# RobotComputerVision_1_1.net
KiCad netlist of a schematic drawn in Altium Designer
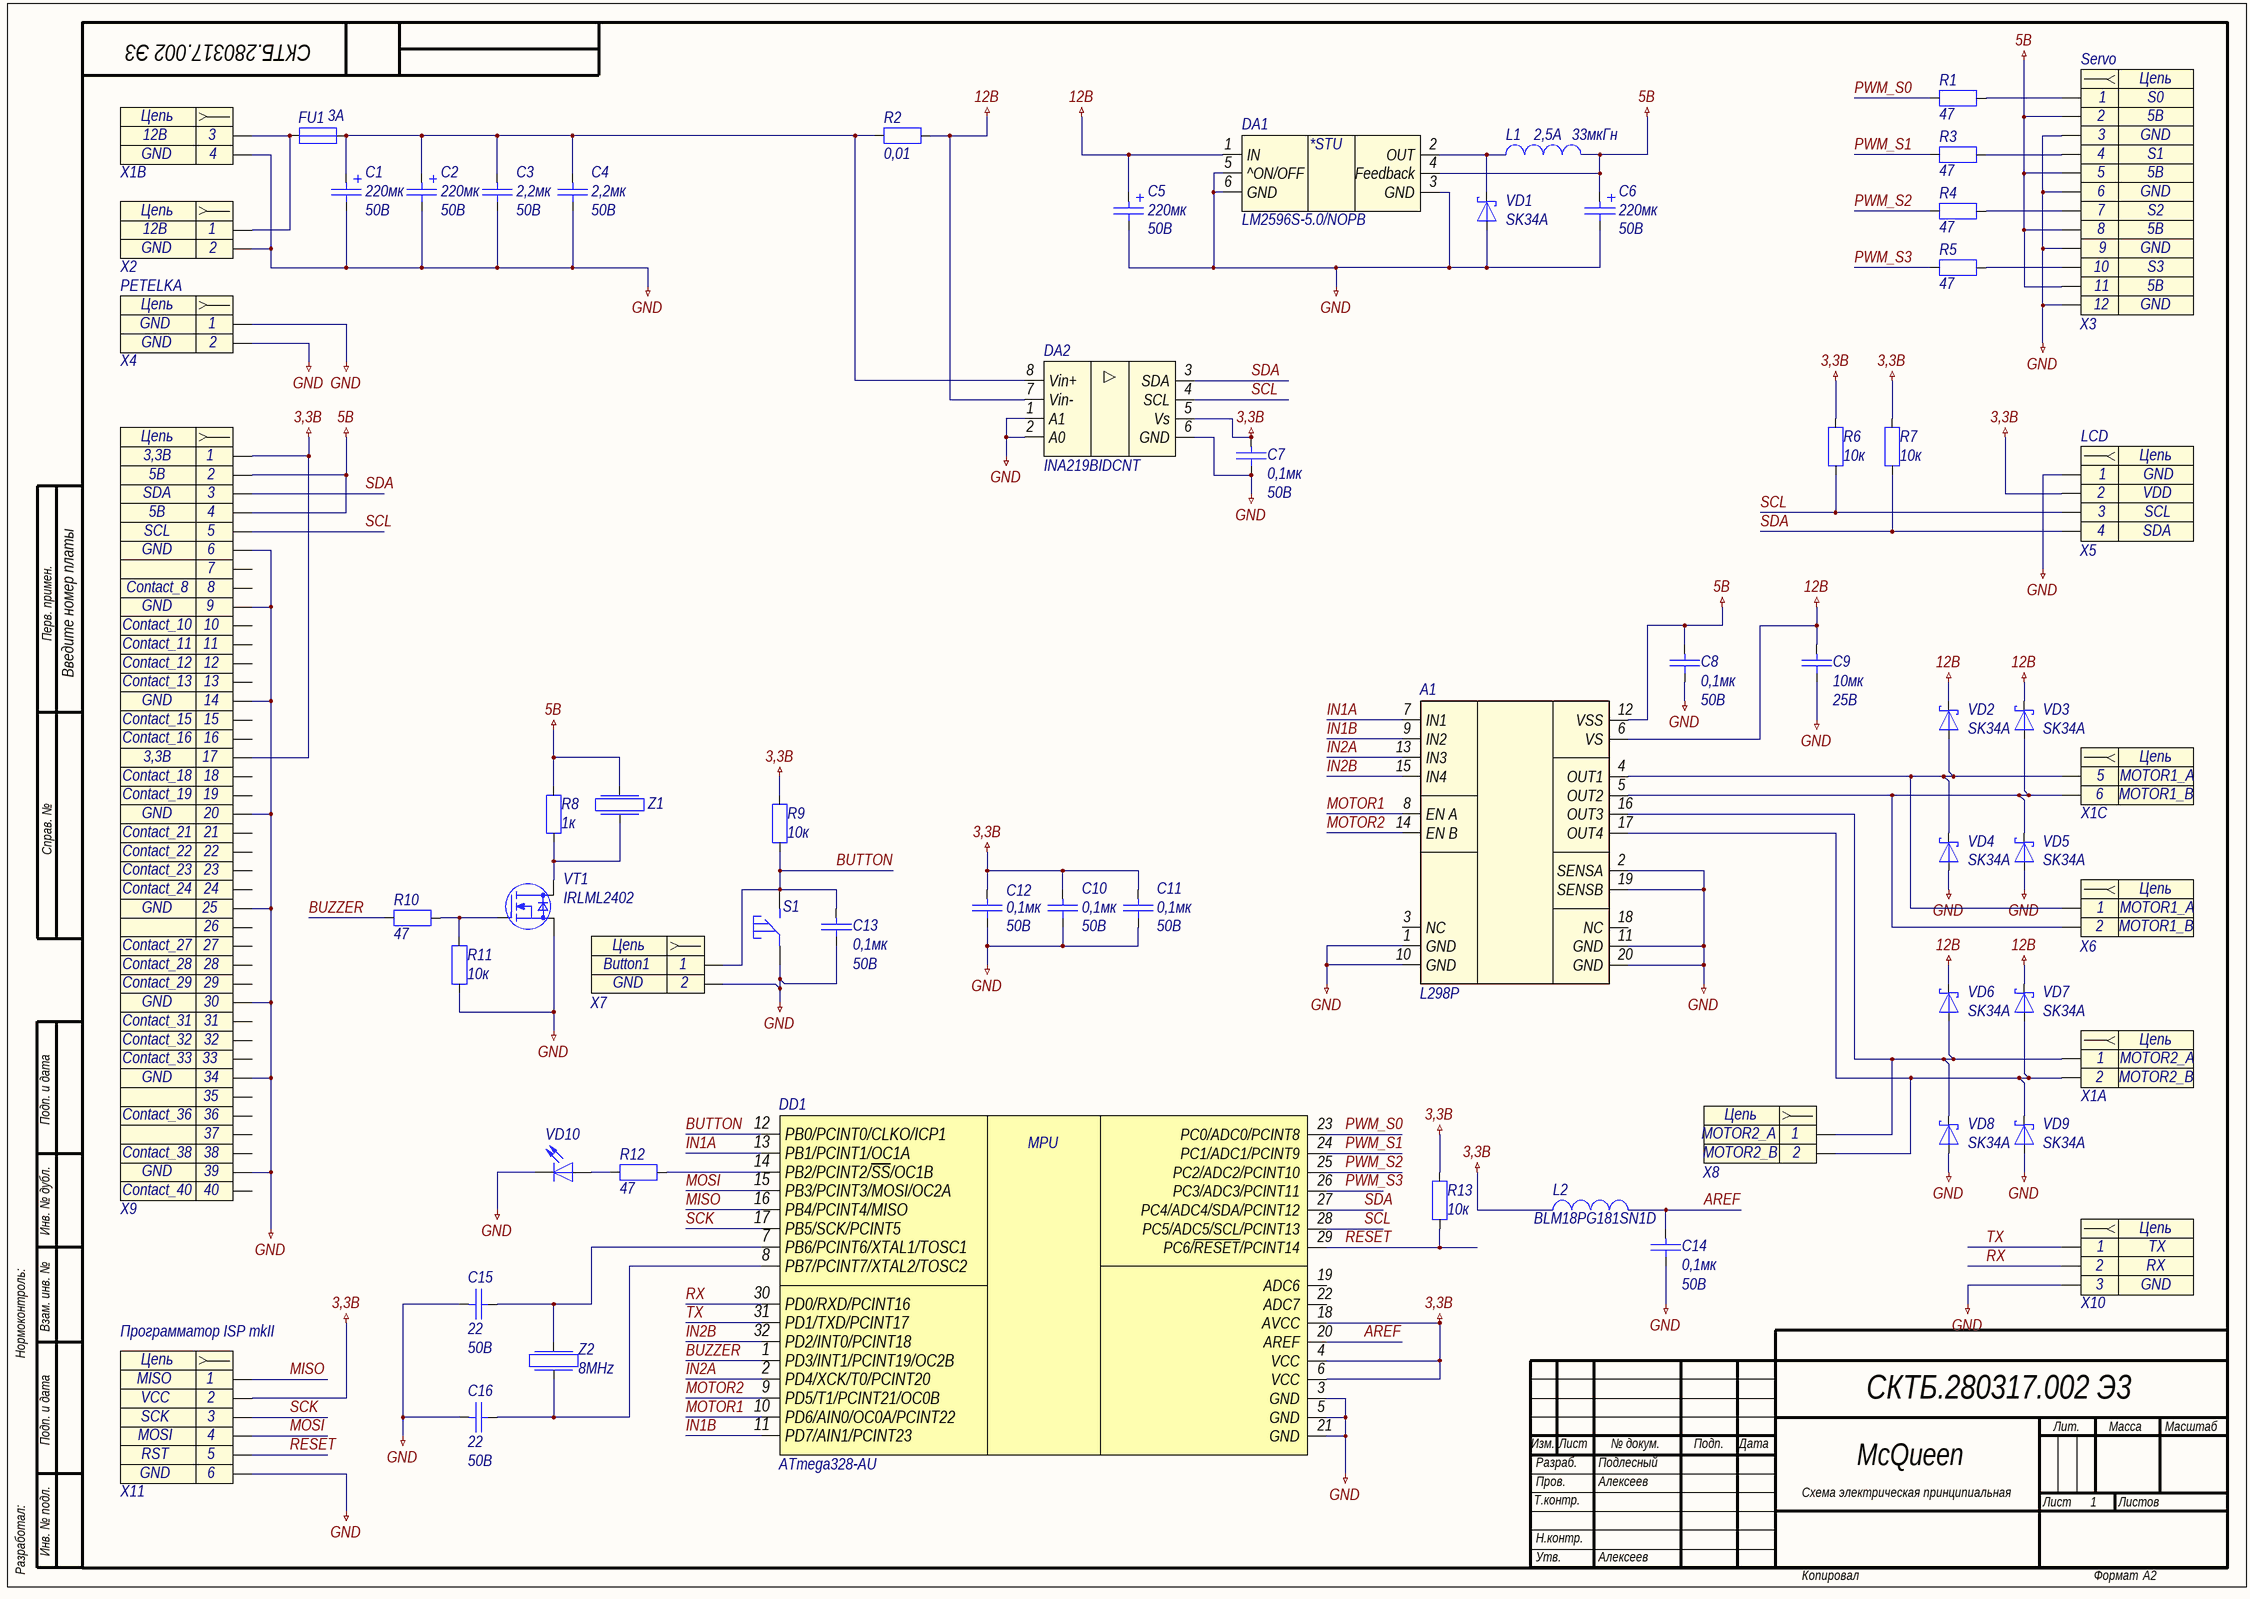
[diagram p0: RobotComputerVision_1.1.SchDoc]

(export (version "E")
  (design (tool "Eeschema 10.0.6"))
  (components
    (comp (ref "A1")
      (value "L298P")
      (footprint "ZabugorLib:POWERSO20_N")
      (description "FULL BRIDGE DC MOTOR DRIVER")
      (libsource (lib "ZabugorLib") (part "L298"))
    )
    (comp (ref "C1")
      (value "220мк")
      (footprint "ZabugorLib:Cap_SMD_radial_polar(10x10.5)")
      (description "Конденсатор полярный")
      (fields (field (name "VOLTAGE") "50В"))
      (libsource (lib "ZabugorLib") (part "Capacitor_pol"))
    )
    (comp (ref "C2")
      (value "220мк")
      (footprint "ZabugorLib:Cap_SMD_radial_polar(10x10.5)")
      (description "Конденсатор полярный")
      (fields (field (name "VOLTAGE") "50В"))
      (libsource (lib "ZabugorLib") (part "Capacitor_pol"))
    )
    (comp (ref "C3")
      (value "2,2мк")
      (footprint "ZabugorLib:C0805")
      (description "Конденсатор")
      (fields (field (name "VOLTAGE") "50В"))
      (libsource (lib "ZabugorLib") (part "Capacitor"))
    )
    (comp (ref "C4")
      (value "2,2мк")
      (footprint "ZabugorLib:C0805")
      (description "Конденсатор")
      (fields (field (name "VOLTAGE") "50В"))
      (libsource (lib "ZabugorLib") (part "Capacitor"))
    )
    (comp (ref "C5")
      (value "220мк")
      (footprint "ZabugorLib:Cap_SMD_radial_polar(10x10.5)")
      (description "Конденсатор полярный")
      (fields (field (name "VOLTAGE") "50В"))
      (libsource (lib "ZabugorLib") (part "Capacitor_pol"))
    )
    (comp (ref "C6")
      (value "220мк")
      (footprint "ZabugorLib:Cap_SMD_radial_polar(10x10.5)")
      (description "Конденсатор полярный")
      (fields (field (name "VOLTAGE") "50В"))
      (libsource (lib "ZabugorLib") (part "Capacitor_pol"))
    )
    (comp (ref "C7")
      (value "0,1мк")
      (footprint "ZabugorLib:C0805")
      (description "Конденсатор")
      (fields (field (name "VOLTAGE") "50В"))
      (libsource (lib "ZabugorLib") (part "Capacitor"))
    )
    (comp (ref "C8")
      (value "0,1мк")
      (footprint "ZabugorLib:C0805")
      (description "Конденсатор")
      (fields (field (name "VOLTAGE") "50В"))
      (libsource (lib "ZabugorLib") (part "Capacitor"))
    )
    (comp (ref "C9")
      (value "10мк")
      (footprint "ZabugorLib:C1210")
      (description "Конденсатор")
      (fields (field (name "VOLTAGE") "25В"))
      (libsource (lib "ZabugorLib") (part "Capacitor"))
    )
    (comp (ref "C10")
      (value "0,1мк")
      (footprint "ZabugorLib:C0805")
      (description "Конденсатор")
      (fields (field (name "VOLTAGE") "50В"))
      (libsource (lib "ZabugorLib") (part "Capacitor"))
    )
    (comp (ref "C11")
      (value "0,1мк")
      (footprint "ZabugorLib:C0805")
      (description "Конденсатор")
      (fields (field (name "VOLTAGE") "50В"))
      (libsource (lib "ZabugorLib") (part "Capacitor"))
    )
    (comp (ref "C12")
      (value "0,1мк")
      (footprint "ZabugorLib:C0805")
      (description "Конденсатор")
      (fields (field (name "VOLTAGE") "50В"))
      (libsource (lib "ZabugorLib") (part "Capacitor"))
    )
    (comp (ref "C13")
      (value "0,1мк")
      (footprint "ZabugorLib:C0805")
      (description "Конденсатор")
      (fields (field (name "VOLTAGE") "50В"))
      (libsource (lib "ZabugorLib") (part "Capacitor"))
    )
    (comp (ref "C14")
      (value "0,1мк")
      (footprint "ZabugorLib:C0805")
      (description "Конденсатор")
      (fields (field (name "VOLTAGE") "50В"))
      (libsource (lib "ZabugorLib") (part "Capacitor"))
    )
    (comp (ref "C15")
      (value "22")
      (footprint "ZabugorLib:C0805")
      (description "Конденсатор")
      (fields (field (name "VOLTAGE") "50В"))
      (libsource (lib "ZabugorLib") (part "Capacitor"))
    )
    (comp (ref "C16")
      (value "22")
      (footprint "ZabugorLib:C0805")
      (description "Конденсатор")
      (fields (field (name "VOLTAGE") "50В"))
      (libsource (lib "ZabugorLib") (part "Capacitor"))
    )
    (comp (ref "DA1")
      (value "LM2596S-5.0/NOPB")
      (footprint "ZabugorLib:TO-263")
      (description "3-A Step-Down Voltage Regulator")
      (libsource (lib "ZabugorLib") (part "LM2596"))
    )
    (comp (ref "DA2")
      (value "INA219BIDCNT")
      (footprint "ZabugorLib:SO8")
      (description "Токочувствительный усилитель")
      (libsource (lib "ZabugorLib") (part "INA219"))
    )
    (comp (ref "DD1")
      (value "ATmega328-AU")
      (footprint "ZabugorLib:TQFP-32")
      (description "Микроконтроллер 8-Бит, AVR, 16МГц, 8КБ Flash")
      (fields (field (name "NAME") "ATmega328-AU"))
      (libsource (lib "ZabugorLib") (part "ATmega328-AU"))
    )
    (comp (ref "FU1")
      (value "3А")
      (footprint "ZabugorLib:MF-R300")
      (description "Предохранитель")
      (fields (field (name "Comment") "MF-R300"))
      (libsource (lib "ZabugorLib") (part "Fuse"))
    )
    (comp (ref "L1")
      (value "33мкГн")
      (footprint "ZabugorLib:SRR1208")
      (description "Катушка индуктивности")
      (fields (field (name "IMAX") "2,5А"))
      (libsource (lib "ZabugorLib") (part "Inductor"))
    )
    (comp (ref "L2")
      (value "~")
      (footprint "ZabugorLib:L0603")
      (description "Катушка индуктивности")
      (fields (field (name "NAME") "BLM18PG181SN1D"))
      (libsource (lib "ZabugorLib") (part "Inductor"))
    )
    (comp (ref "R1")
      (value "47")
      (footprint "ZabugorLib:R0805")
      (description "Резистор")
      (libsource (lib "ZabugorLib") (part "Resistor"))
    )
    (comp (ref "R2")
      (value "0,01")
      (footprint "ZabugorLib:R2512")
      (description "Резистор")
      (libsource (lib "") (part "Resistor_2"))
    )
    (comp (ref "R3")
      (value "47")
      (footprint "ZabugorLib:R0805")
      (description "Резистор")
      (libsource (lib "ZabugorLib") (part "Resistor"))
    )
    (comp (ref "R4")
      (value "47")
      (footprint "ZabugorLib:R0805")
      (description "Резистор")
      (libsource (lib "ZabugorLib") (part "Resistor"))
    )
    (comp (ref "R5")
      (value "47")
      (footprint "ZabugorLib:R0805")
      (description "Резистор")
      (libsource (lib "ZabugorLib") (part "Resistor"))
    )
    (comp (ref "R6")
      (value "10к")
      (footprint "ZabugorLib:R0805")
      (description "Резистор")
      (libsource (lib "") (part "Resistor_2"))
    )
    (comp (ref "R7")
      (value "10к")
      (footprint "ZabugorLib:R0805")
      (description "Резистор")
      (libsource (lib "") (part "Resistor_2"))
    )
    (comp (ref "R8")
      (value "1к")
      (footprint "ZabugorLib:R0805")
      (description "Резистор")
      (libsource (lib "ZabugorLib") (part "Resistor"))
    )
    (comp (ref "R9")
      (value "10к")
      (footprint "ZabugorLib:R0805")
      (description "Резистор")
      (libsource (lib "ZabugorLib") (part "Resistor"))
    )
    (comp (ref "R10")
      (value "47")
      (footprint "ZabugorLib:R0805")
      (description "Резистор")
      (libsource (lib "") (part "Resistor_1"))
    )
    (comp (ref "R11")
      (value "10к")
      (footprint "ZabugorLib:R0805")
      (description "Резистор")
      (libsource (lib "ZabugorLib") (part "Resistor"))
    )
    (comp (ref "R12")
      (value "47")
      (footprint "ZabugorLib:R0805")
      (description "Резистор")
      (libsource (lib "") (part "Resistor_1"))
    )
    (comp (ref "R13")
      (value "10к")
      (footprint "ZabugorLib:R0805")
      (description "Резистор")
      (libsource (lib "ZabugorLib") (part "Resistor"))
    )
    (comp (ref "S1")
      (value "~")
      (footprint "ZabugorLib:Button_SMD")
      (description "Кнопка")
      (libsource (lib "ZabugorLib") (part "Button_SMD"))
    )
    (comp (ref "VD1")
      (value "SK34A")
      (footprint "ZabugorLib:SMA")
      (description "Диод Шоттки")
      (fields (field (name "NAME") "SK34A"))
      (libsource (lib "ZabugorLib") (part "DiodeSchottky"))
    )
    (comp (ref "VD2")
      (value "SK34A")
      (footprint "ZabugorLib:SMA")
      (description "Диод Шоттки")
      (fields (field (name "NAME") "SK34A"))
      (libsource (lib "ZabugorLib") (part "DiodeSchottky"))
    )
    (comp (ref "VD3")
      (value "SK34A")
      (footprint "ZabugorLib:SMA")
      (description "Диод Шоттки")
      (fields (field (name "NAME") "SK34A"))
      (libsource (lib "ZabugorLib") (part "DiodeSchottky"))
    )
    (comp (ref "VD4")
      (value "SK34A")
      (footprint "ZabugorLib:SMA")
      (description "Диод Шоттки")
      (fields (field (name "NAME") "SK34A"))
      (libsource (lib "ZabugorLib") (part "DiodeSchottky"))
    )
    (comp (ref "VD5")
      (value "SK34A")
      (footprint "ZabugorLib:SMA")
      (description "Диод Шоттки")
      (fields (field (name "NAME") "SK34A"))
      (libsource (lib "ZabugorLib") (part "DiodeSchottky"))
    )
    (comp (ref "VD6")
      (value "SK34A")
      (footprint "ZabugorLib:SMA")
      (description "Диод Шоттки")
      (fields (field (name "NAME") "SK34A"))
      (libsource (lib "ZabugorLib") (part "DiodeSchottky"))
    )
    (comp (ref "VD7")
      (value "SK34A")
      (footprint "ZabugorLib:SMA")
      (description "Диод Шоттки")
      (fields (field (name "NAME") "SK34A"))
      (libsource (lib "ZabugorLib") (part "DiodeSchottky"))
    )
    (comp (ref "VD8")
      (value "SK34A")
      (footprint "ZabugorLib:SMA")
      (description "Диод Шоттки")
      (fields (field (name "NAME") "SK34A"))
      (libsource (lib "ZabugorLib") (part "DiodeSchottky"))
    )
    (comp (ref "VD9")
      (value "SK34A")
      (footprint "ZabugorLib:SMA")
      (description "Диод Шоттки")
      (fields (field (name "NAME") "SK34A"))
      (libsource (lib "ZabugorLib") (part "DiodeSchottky"))
    )
    (comp (ref "VD10")
      (value "~")
      (footprint "ZabugorLib:D0805")
      (description "Светодиод")
      (libsource (lib "ZabugorLib") (part "LED_L"))
    )
    (comp (ref "VT1")
      (value "IRLML2402")
      (footprint "Stove_Light:SOT23-3_H")
      (description "N-MOSFET")
      (libsource (lib "ZabugorLib") (part "N-MOSFET"))
    )
    (comp (ref "X1")
      (value "~")
      (footprint "ZabugorLib:DT-128V-6")
      (description "POWER")
      (libsource (lib "ZabugorLib") (part "Header_6_motor"))
    )
    (comp (ref "X2")
      (value "~")
      (footprint "ZabugorLib:2HOLE_2.5")
      (description "Разъем - 2 конт. розетка")
      (libsource (lib "ZabugorLib") (part "Header_2_sct"))
    )
    (comp (ref "X3")
      (value "Servo")
      (footprint "ZabugorLib:PLS-12")
      (description "Разъем - 5 конт. розетка")
      (libsource (lib "ZabugorLib") (part "Header_12"))
    )
    (comp (ref "X4")
      (value "PETELKA")
      (footprint "ZabugorLib:2HOLE_PETELKA")
      (description "Разъем - 2 конт. розетка")
      (fields (field (name "NAME") "PETELKA"))
      (libsource (lib "ZabugorLib") (part "Header_2_sct"))
    )
    (comp (ref "X5")
      (value "LCD")
      (footprint "ZabugorLib:PLS-4holes")
      (description "Разъем - 4 конт. розетка")
      (fields (field (name "NAME") "LCD"))
      (libsource (lib "ZabugorLib") (part "Header_4_sct"))
    )
    (comp (ref "X6")
      (value "~")
      (footprint "ZabugorLib:2HOLE_2.5")
      (description "Разъем - 2 конт. розетка")
      (libsource (lib "") (part "Header_2_sct_1"))
    )
    (comp (ref "X7")
      (value "~")
      (footprint "ZabugorLib:2HOLE_2.5")
      (description "Разъем - 2 конт. розетка")
      (libsource (lib "ZabugorLib") (part "Header_2_sct"))
    )
    (comp (ref "X8")
      (value "~")
      (footprint "ZabugorLib:2HOLE_2.5")
      (description "Разъем - 2 конт. розетка")
      (libsource (lib "ZabugorLib") (part "Header_2_sct"))
    )
    (comp (ref "X9")
      (value "~")
      (footprint "ZabugorLib:PBS-40")
      (description "Разъем - 5 конт. розетка")
      (libsource (lib "ZabugorLib") (part "Header_40"))
    )
    (comp (ref "X10")
      (value "~")
      (footprint "ZabugorLib:PLS2-3holes")
      (description "Разъем - 2 конт. розетка")
      (libsource (lib "ZabugorLib") (part "Header_3_sct"))
    )
    (comp (ref "X11")
      (value "Программатор ISP mkII")
      (footprint "ZabugorLib:PLS2-6")
      (description "Разъем - 5 конт. розетка")
      (libsource (lib "ZabugorLib") (part "Header_6_sct"))
    )
    (comp (ref "Z1")
      (value "XXX")
      (footprint "ZabugorLib:Пьезоизлучатель звуковой")
      (description "Пьезоизлучатель звуковой")
      (libsource (lib "ZabugorLib") (part "Buzzer"))
    )
    (comp (ref "Z2")
      (value "8MHz")
      (footprint "ZabugorLib:QSMD5.0x3.2x1.0")
      (description "Кварцевый резонатор")
      (libsource (lib "ZabugorLib") (part "Crystal"))
    )
  )
  (nets
    (net (code "1") (name "/AREF") (class "Default")
      (node (ref "C14") (pin "1") (pinfunction "1_1") (pintype "passive"))
      (node (ref "DD1") (pin "20") (pinfunction "AREF_20") (pintype "passive"))
      (node (ref "L2") (pin "2") (pinfunction "2_2") (pintype "passive"))
    )
    (net (code "2") (name "/BUTTON") (class "Default")
      (node (ref "C13") (pin "1") (pinfunction "1_1") (pintype "passive"))
      (node (ref "DD1") (pin "12") (pinfunction "PB0/PCINT0/CLKO/ICP1_12") (pintype "passive"))
      (node (ref "R9") (pin "1") (pinfunction "1_1") (pintype "passive"))
      (node (ref "S1") (pin "4") (pinfunction "4_4") (pintype "passive"))
      (node (ref "X7") (pin "1") (pinfunction "1_1") (pintype "passive"))
    )
    (net (code "3") (name "/BUZZER") (class "Default")
      (node (ref "DD1") (pin "1") (pinfunction "PD3/INT1/PCINT19/OC2B_1") (pintype "passive"))
      (node (ref "R10") (pin "2") (pinfunction "2_2") (pintype "passive"))
    )
    (net (code "4") (name "/IN1A") (class "Default")
      (node (ref "A1") (pin "7") (pinfunction "IN1_7") (pintype "passive"))
      (node (ref "DD1") (pin "13") (pinfunction "PB1/PCINT1/OC1A_13") (pintype "passive"))
    )
    (net (code "5") (name "/IN1B") (class "Default")
      (node (ref "A1") (pin "9") (pinfunction "IN2_9") (pintype "passive"))
      (node (ref "DD1") (pin "11") (pinfunction "PD7/AIN1/PCINT23_11") (pintype "passive"))
    )
    (net (code "6") (name "/IN2A") (class "Default")
      (node (ref "A1") (pin "13") (pinfunction "IN3_13") (pintype "passive"))
      (node (ref "DD1") (pin "2") (pinfunction "PD4/XCK/T0/PCINT20_2") (pintype "passive"))
    )
    (net (code "7") (name "/IN2B") (class "Default")
      (node (ref "A1") (pin "15") (pinfunction "IN4_15") (pintype "passive"))
      (node (ref "DD1") (pin "32") (pinfunction "PD2/INT0/PCINT18_32") (pintype "passive"))
    )
    (net (code "8") (name "/MISO") (class "Default")
      (node (ref "DD1") (pin "16") (pinfunction "PB4/PCINT4/MISO_16") (pintype "passive"))
      (node (ref "X11") (pin "1") (pinfunction "1_1") (pintype "passive"))
    )
    (net (code "9") (name "/MOSI") (class "Default")
      (node (ref "DD1") (pin "15") (pinfunction "PB3/PCINT3/MOSI/OC2A_15") (pintype "passive"))
      (node (ref "X11") (pin "4") (pinfunction "4_4") (pintype "passive"))
    )
    (net (code "10") (name "/MOTOR1") (class "Default")
      (node (ref "A1") (pin "8") (pinfunction "EN_A_8") (pintype "passive"))
      (node (ref "DD1") (pin "10") (pinfunction "PD6/AIN0/OC0A/PCINT22_10") (pintype "passive"))
    )
    (net (code "11") (name "/MOTOR2") (class "Default")
      (node (ref "A1") (pin "14") (pinfunction "EN_B_14") (pintype "passive"))
      (node (ref "DD1") (pin "9") (pinfunction "PD5/T1/PCINT21/OC0B_9") (pintype "passive"))
    )
    (net (code "12") (name "/PWM_S0") (class "Default")
      (node (ref "DD1") (pin "23") (pinfunction "PC0/ADC0/PCINT8_23") (pintype "passive"))
      (node (ref "R1") (pin "1") (pinfunction "1_1") (pintype "passive"))
    )
    (net (code "13") (name "/PWM_S1") (class "Default")
      (node (ref "DD1") (pin "24") (pinfunction "PC1/ADC1/PCINT9_24") (pintype "passive"))
      (node (ref "R3") (pin "1") (pinfunction "1_1") (pintype "passive"))
    )
    (net (code "14") (name "/PWM_S2") (class "Default")
      (node (ref "DD1") (pin "25") (pinfunction "PC2/ADC2/PCINT10_25") (pintype "passive"))
      (node (ref "R4") (pin "1") (pinfunction "1_1") (pintype "passive"))
    )
    (net (code "15") (name "/PWM_S3") (class "Default")
      (node (ref "DD1") (pin "26") (pinfunction "PC3/ADC3/PCINT11_26") (pintype "passive"))
      (node (ref "R5") (pin "1") (pinfunction "1_1") (pintype "passive"))
    )
    (net (code "16") (name "/RESET") (class "Default")
      (node (ref "DD1") (pin "29") (pinfunction "PC6/~{RESET}/PCINT14_29") (pintype "passive"))
      (node (ref "R13") (pin "1") (pinfunction "1_1") (pintype "passive"))
      (node (ref "X11") (pin "5") (pinfunction "5_5") (pintype "passive"))
    )
    (net (code "17") (name "/RX") (class "Default")
      (node (ref "DD1") (pin "30") (pinfunction "PD0/RXD/PCINT16_30") (pintype "passive"))
      (node (ref "X10") (pin "2") (pinfunction "2_2") (pintype "passive"))
    )
    (net (code "18") (name "/SCK") (class "Default")
      (node (ref "DD1") (pin "17") (pinfunction "PB5/SCK/PCINT5_17") (pintype "passive"))
      (node (ref "X11") (pin "3") (pinfunction "3_3") (pintype "passive"))
    )
    (net (code "19") (name "/SCL") (class "Default")
      (node (ref "DA2") (pin "4") (pinfunction "SCL_4") (pintype "passive"))
      (node (ref "DD1") (pin "28") (pinfunction "PC5/ADC5/SCL/PCINT13_28") (pintype "passive"))
      (node (ref "R6") (pin "1") (pinfunction "1_1") (pintype "passive"))
      (node (ref "X5") (pin "3") (pinfunction "3_3") (pintype "passive"))
      (node (ref "X9") (pin "5") (pinfunction "5_5") (pintype "passive"))
    )
    (net (code "20") (name "/SDA") (class "Default")
      (node (ref "DA2") (pin "3") (pinfunction "SDA_3") (pintype "passive"))
      (node (ref "DD1") (pin "27") (pinfunction "PC4/ADC4/SDA/PCINT12_27") (pintype "passive"))
      (node (ref "R7") (pin "1") (pinfunction "1_1") (pintype "passive"))
      (node (ref "X5") (pin "4") (pinfunction "4_4") (pintype "passive"))
      (node (ref "X9") (pin "3") (pinfunction "3_3") (pintype "passive"))
    )
    (net (code "21") (name "/TX") (class "Default")
      (node (ref "DD1") (pin "31") (pinfunction "PD1/TXD/PCINT17_31") (pintype "passive"))
      (node (ref "X10") (pin "1") (pinfunction "1_1") (pintype "passive"))
    )
    (net (code "22") (name "3,3B") (class "Default")
      (node (ref "C10") (pin "1") (pinfunction "1_1") (pintype "passive"))
      (node (ref "C11") (pin "1") (pinfunction "1_1") (pintype "passive"))
      (node (ref "C12") (pin "1") (pinfunction "1_1") (pintype "passive"))
      (node (ref "C7") (pin "1") (pinfunction "1_1") (pintype "passive"))
      (node (ref "DA2") (pin "5") (pinfunction "Vs_5") (pintype "passive"))
      (node (ref "DD1") (pin "18") (pinfunction "AVCC_18") (pintype "passive"))
      (node (ref "DD1") (pin "4") (pinfunction "VCC_4") (pintype "passive"))
      (node (ref "DD1") (pin "6") (pinfunction "VCC_6") (pintype "passive"))
      (node (ref "L2") (pin "1") (pinfunction "1_1") (pintype "passive"))
      (node (ref "R13") (pin "2") (pinfunction "2_2") (pintype "passive"))
      (node (ref "R6") (pin "2") (pinfunction "2_2") (pintype "passive"))
      (node (ref "R7") (pin "2") (pinfunction "2_2") (pintype "passive"))
      (node (ref "R9") (pin "2") (pinfunction "2_2") (pintype "passive"))
      (node (ref "X11") (pin "2") (pinfunction "2_2") (pintype "passive"))
      (node (ref "X5") (pin "2") (pinfunction "2_2") (pintype "passive"))
      (node (ref "X9") (pin "1") (pinfunction "1_1") (pintype "passive"))
      (node (ref "X9") (pin "17") (pinfunction "17_17") (pintype "passive"))
    )
    (net (code "23") (name "5В") (class "Default")
      (node (ref "A1") (pin "12") (pinfunction "VSS_12") (pintype "passive"))
      (node (ref "C6") (pin "1") (pinfunction "1_1") (pintype "passive"))
      (node (ref "C8") (pin "1") (pinfunction "1_1") (pintype "passive"))
      (node (ref "DA1") (pin "4") (pinfunction "Feedback_4") (pintype "power_in"))
      (node (ref "L1") (pin "2") (pinfunction "2_2") (pintype "passive"))
      (node (ref "R8") (pin "2") (pinfunction "2_2") (pintype "passive"))
      (node (ref "X3") (pin "11") (pinfunction "11_11") (pintype "passive"))
      (node (ref "X3") (pin "2") (pinfunction "2_2") (pintype "passive"))
      (node (ref "X3") (pin "5") (pinfunction "5_5") (pintype "passive"))
      (node (ref "X3") (pin "8") (pinfunction "8_8") (pintype "passive"))
      (node (ref "X9") (pin "2") (pinfunction "2_2") (pintype "passive"))
      (node (ref "X9") (pin "4") (pinfunction "4_4") (pintype "passive"))
      (node (ref "Z1") (pin "1") (pinfunction "1_1") (pintype "passive"))
    )
    (net (code "24") (name "12В") (class "Default")
      (node (ref "A1") (pin "6") (pinfunction "VS_6") (pintype "passive"))
      (node (ref "C5") (pin "1") (pinfunction "1_1") (pintype "passive"))
      (node (ref "C9") (pin "1") (pinfunction "1_1") (pintype "passive"))
      (node (ref "DA1") (pin "1") (pinfunction "IN_1") (pintype "power_in"))
      (node (ref "DA2") (pin "7") (pinfunction "Vin-_7") (pintype "passive"))
      (node (ref "R2") (pin "2") (pinfunction "2_2") (pintype "passive"))
      (node (ref "VD2") (pin "1") (pinfunction "K_1") (pintype "passive"))
      (node (ref "VD3") (pin "1") (pinfunction "K_1") (pintype "passive"))
      (node (ref "VD6") (pin "1") (pinfunction "K_1") (pintype "passive"))
      (node (ref "VD7") (pin "1") (pinfunction "K_1") (pintype "passive"))
    )
    (net (code "25") (name "GND") (class "Default")
      (node (ref "A1") (pin "1") (pinfunction "GND_1") (pintype "passive"))
      (node (ref "A1") (pin "10") (pinfunction "GND_10") (pintype "passive"))
      (node (ref "A1") (pin "11") (pinfunction "GND_11") (pintype "passive"))
      (node (ref "A1") (pin "19") (pinfunction "SENSB_19") (pintype "passive"))
      (node (ref "A1") (pin "2") (pinfunction "SENSA_2") (pintype "passive"))
      (node (ref "A1") (pin "20") (pinfunction "GND_20") (pintype "passive"))
      (node (ref "C1") (pin "2") (pinfunction "2_2") (pintype "passive"))
      (node (ref "C10") (pin "2") (pinfunction "2_2") (pintype "passive"))
      (node (ref "C11") (pin "2") (pinfunction "2_2") (pintype "passive"))
      (node (ref "C12") (pin "2") (pinfunction "2_2") (pintype "passive"))
      (node (ref "C13") (pin "2") (pinfunction "2_2") (pintype "passive"))
      (node (ref "C14") (pin "2") (pinfunction "2_2") (pintype "passive"))
      (node (ref "C15") (pin "1") (pinfunction "1_1") (pintype "passive"))
      (node (ref "C16") (pin "1") (pinfunction "1_1") (pintype "passive"))
      (node (ref "C2") (pin "2") (pinfunction "2_2") (pintype "passive"))
      (node (ref "C3") (pin "2") (pinfunction "2_2") (pintype "passive"))
      (node (ref "C4") (pin "2") (pinfunction "2_2") (pintype "passive"))
      (node (ref "C5") (pin "2") (pinfunction "2_2") (pintype "passive"))
      (node (ref "C6") (pin "2") (pinfunction "2_2") (pintype "passive"))
      (node (ref "C7") (pin "2") (pinfunction "2_2") (pintype "passive"))
      (node (ref "C8") (pin "2") (pinfunction "2_2") (pintype "passive"))
      (node (ref "C9") (pin "2") (pinfunction "2_2") (pintype "passive"))
      (node (ref "DA1") (pin "3") (pinfunction "GND_3") (pintype "power_in"))
      (node (ref "DA1") (pin "5") (pinfunction "^ON/OFF_5") (pintype "power_in"))
      (node (ref "DA1") (pin "6") (pinfunction "GND_6") (pintype "power_in"))
      (node (ref "DA2") (pin "1") (pinfunction "A1_1") (pintype "passive"))
      (node (ref "DA2") (pin "2") (pinfunction "A0_2") (pintype "passive"))
      (node (ref "DA2") (pin "6") (pinfunction "GND_6") (pintype "passive"))
      (node (ref "DD1") (pin "21") (pinfunction "GND_21") (pintype "passive"))
      (node (ref "DD1") (pin "3") (pinfunction "GND_3") (pintype "passive"))
      (node (ref "DD1") (pin "5") (pinfunction "GND_5") (pintype "passive"))
      (node (ref "R11") (pin "1") (pinfunction "1_1") (pintype "passive"))
      (node (ref "S1") (pin "1") (pinfunction "1_1") (pintype "passive"))
      (node (ref "VD1") (pin "2") (pinfunction "A_2") (pintype "passive"))
      (node (ref "VD10") (pin "1") (pinfunction "K_1") (pintype "passive"))
      (node (ref "VD4") (pin "2") (pinfunction "A_2") (pintype "passive"))
      (node (ref "VD5") (pin "2") (pinfunction "A_2") (pintype "passive"))
      (node (ref "VD8") (pin "2") (pinfunction "A_2") (pintype "passive"))
      (node (ref "VD9") (pin "2") (pinfunction "A_2") (pintype "passive"))
      (node (ref "VT1") (pin "2") (pinfunction "S_2") (pintype "passive"))
      (node (ref "X1") (pin "4") (pinfunction "4_4") (pintype "passive"))
      (node (ref "X10") (pin "3") (pinfunction "3_3") (pintype "passive"))
      (node (ref "X11") (pin "6") (pinfunction "6_6") (pintype "passive"))
      (node (ref "X2") (pin "2") (pinfunction "2_2") (pintype "passive"))
      (node (ref "X3") (pin "12") (pinfunction "12_12") (pintype "passive"))
      (node (ref "X3") (pin "3") (pinfunction "3_3") (pintype "passive"))
      (node (ref "X3") (pin "6") (pinfunction "6_6") (pintype "passive"))
      (node (ref "X3") (pin "9") (pinfunction "9_9") (pintype "passive"))
      (node (ref "X4") (pin "1") (pinfunction "1_1") (pintype "passive"))
      (node (ref "X4") (pin "2") (pinfunction "2_2") (pintype "passive"))
      (node (ref "X5") (pin "1") (pinfunction "1_1") (pintype "passive"))
      (node (ref "X7") (pin "2") (pinfunction "2_2") (pintype "passive"))
      (node (ref "X9") (pin "14") (pinfunction "14_14") (pintype "passive"))
      (node (ref "X9") (pin "20") (pinfunction "20_20") (pintype "passive"))
      (node (ref "X9") (pin "25") (pinfunction "25_25") (pintype "passive"))
      (node (ref "X9") (pin "30") (pinfunction "30_30") (pintype "passive"))
      (node (ref "X9") (pin "34") (pinfunction "34_34") (pintype "passive"))
      (node (ref "X9") (pin "39") (pinfunction "39_39") (pintype "passive"))
      (node (ref "X9") (pin "6") (pinfunction "6_6") (pintype "passive"))
      (node (ref "X9") (pin "9") (pinfunction "9_9") (pintype "passive"))
    )
    (net (code "26") (name "Net-(A1-OUT1)") (class "Default")
      (node (ref "A1") (pin "4") (pinfunction "OUT1_4") (pintype "passive"))
      (node (ref "VD2") (pin "2") (pinfunction "A_2") (pintype "passive"))
      (node (ref "VD4") (pin "1") (pinfunction "K_1") (pintype "passive"))
      (node (ref "X1") (pin "5") (pinfunction "5_5") (pintype "passive"))
      (node (ref "X6") (pin "1") (pinfunction "1_1") (pintype "passive"))
    )
    (net (code "27") (name "Net-(A1-OUT2)") (class "Default")
      (node (ref "A1") (pin "5") (pinfunction "OUT2_5") (pintype "passive"))
      (node (ref "VD3") (pin "2") (pinfunction "A_2") (pintype "passive"))
      (node (ref "VD5") (pin "1") (pinfunction "K_1") (pintype "passive"))
      (node (ref "X1") (pin "6") (pinfunction "6_6") (pintype "passive"))
      (node (ref "X6") (pin "2") (pinfunction "2_2") (pintype "passive"))
    )
    (net (code "28") (name "Net-(A1-OUT3)") (class "Default")
      (node (ref "A1") (pin "16") (pinfunction "OUT3_16") (pintype "passive"))
      (node (ref "VD6") (pin "2") (pinfunction "A_2") (pintype "passive"))
      (node (ref "VD8") (pin "1") (pinfunction "K_1") (pintype "passive"))
      (node (ref "X1") (pin "1") (pinfunction "1_1") (pintype "passive"))
      (node (ref "X8") (pin "1") (pinfunction "1_1") (pintype "passive"))
    )
    (net (code "29") (name "Net-(A1-OUT4)") (class "Default")
      (node (ref "A1") (pin "17") (pinfunction "OUT4_17") (pintype "passive"))
      (node (ref "VD7") (pin "2") (pinfunction "A_2") (pintype "passive"))
      (node (ref "VD9") (pin "1") (pinfunction "K_1") (pintype "passive"))
      (node (ref "X1") (pin "2") (pinfunction "2_2") (pintype "passive"))
      (node (ref "X8") (pin "2") (pinfunction "2_2") (pintype "passive"))
    )
    (net (code "30") (name "Net-(DA1-OUT)") (class "Default")
      (node (ref "DA1") (pin "2") (pinfunction "OUT_2") (pintype "power_in"))
      (node (ref "L1") (pin "1") (pinfunction "1_1") (pintype "passive"))
      (node (ref "VD1") (pin "1") (pinfunction "K_1") (pintype "passive"))
    )
    (net (code "31") (name "Net-(DA2-Vin+)") (class "Default")
      (node (ref "C1") (pin "1") (pinfunction "1_1") (pintype "passive"))
      (node (ref "C2") (pin "1") (pinfunction "1_1") (pintype "passive"))
      (node (ref "C3") (pin "1") (pinfunction "1_1") (pintype "passive"))
      (node (ref "C4") (pin "1") (pinfunction "1_1") (pintype "passive"))
      (node (ref "DA2") (pin "8") (pinfunction "Vin+_8") (pintype "passive"))
      (node (ref "FU1") (pin "2") (pinfunction "2_2") (pintype "passive"))
      (node (ref "R2") (pin "1") (pinfunction "1_1") (pintype "passive"))
    )
    (net (code "32") (name "Net-(DD1-PB2{slash}PCINT2{slash}~{SS}{slash}OC1B)") (class "Default")
      (node (ref "DD1") (pin "14") (pinfunction "PB2/PCINT2/~{SS}/OC1B_14") (pintype "passive"))
      (node (ref "R12") (pin "1") (pinfunction "1_1") (pintype "passive"))
    )
    (net (code "33") (name "Net-(DD1-PB6{slash}PCINT6{slash}XTAL1{slash}TOSC1)") (class "Default")
      (node (ref "C15") (pin "2") (pinfunction "2_2") (pintype "passive"))
      (node (ref "DD1") (pin "7") (pinfunction "PB6/PCINT6/XTAL1/TOSC1_7") (pintype "passive"))
      (node (ref "Z2") (pin "1") (pinfunction "1_1") (pintype "passive"))
    )
    (net (code "34") (name "Net-(DD1-PB7{slash}PCINT7{slash}XTAL2{slash}TOSC2)") (class "Default")
      (node (ref "C16") (pin "2") (pinfunction "2_2") (pintype "passive"))
      (node (ref "DD1") (pin "8") (pinfunction "PB7/PCINT7/XTAL2/TOSC2_8") (pintype "passive"))
      (node (ref "Z2") (pin "2") (pinfunction "2_2") (pintype "passive"))
    )
    (net (code "35") (name "Net-(FU1-Pad1)") (class "Default")
      (node (ref "FU1") (pin "1") (pinfunction "1_1") (pintype "passive"))
      (node (ref "X1") (pin "3") (pinfunction "3_3") (pintype "passive"))
      (node (ref "X2") (pin "1") (pinfunction "1_1") (pintype "passive"))
    )
    (net (code "36") (name "Net-(R1-Pad2)") (class "Default")
      (node (ref "R1") (pin "2") (pinfunction "2_2") (pintype "passive"))
      (node (ref "X3") (pin "1") (pinfunction "1_1") (pintype "passive"))
    )
    (net (code "37") (name "Net-(R3-Pad2)") (class "Default")
      (node (ref "R3") (pin "2") (pinfunction "2_2") (pintype "passive"))
      (node (ref "X3") (pin "4") (pinfunction "4_4") (pintype "passive"))
    )
    (net (code "38") (name "Net-(R4-Pad2)") (class "Default")
      (node (ref "R4") (pin "2") (pinfunction "2_2") (pintype "passive"))
      (node (ref "X3") (pin "7") (pinfunction "7_7") (pintype "passive"))
    )
    (net (code "39") (name "Net-(R5-Pad2)") (class "Default")
      (node (ref "R5") (pin "2") (pinfunction "2_2") (pintype "passive"))
      (node (ref "X3") (pin "10") (pinfunction "10_10") (pintype "passive"))
    )
    (net (code "40") (name "Net-(VD10-A)") (class "Default")
      (node (ref "R12") (pin "2") (pinfunction "2_2") (pintype "passive"))
      (node (ref "VD10") (pin "2") (pinfunction "A_2") (pintype "passive"))
    )
    (net (code "41") (name "Net-(VT1-D)") (class "Default")
      (node (ref "R8") (pin "1") (pinfunction "1_1") (pintype "passive"))
      (node (ref "VT1") (pin "3") (pinfunction "D_3") (pintype "passive"))
      (node (ref "Z1") (pin "2") (pinfunction "2_2") (pintype "passive"))
    )
    (net (code "42") (name "Net-(VT1-G)") (class "Default")
      (node (ref "R10") (pin "1") (pinfunction "1_1") (pintype "passive"))
      (node (ref "R11") (pin "2") (pinfunction "2_2") (pintype "passive"))
      (node (ref "VT1") (pin "1") (pinfunction "G_1") (pintype "passive"))
    )
    (net (code "43") (name "unconnected-(A1-NC-Pad3)") (class "Default")
      (node (ref "A1") (pin "3") (pinfunction "NC_3") (pintype "passive"))
    )
    (net (code "44") (name "unconnected-(A1-NC-Pad18)") (class "Default")
      (node (ref "A1") (pin "18") (pinfunction "NC_18") (pintype "passive"))
    )
    (net (code "45") (name "unconnected-(DD1-ADC6-Pad19)") (class "Default")
      (node (ref "DD1") (pin "19") (pinfunction "ADC6_19") (pintype "passive"))
    )
    (net (code "46") (name "unconnected-(DD1-ADC7-Pad22)") (class "Default")
      (node (ref "DD1") (pin "22") (pinfunction "ADC7_22") (pintype "passive"))
    )
    (net (code "47") (name "unconnected-(X9-Pad7)") (class "Default")
      (node (ref "X9") (pin "7") (pinfunction "7_7") (pintype "passive"))
    )
    (net (code "48") (name "unconnected-(X9-Pad8)") (class "Default")
      (node (ref "X9") (pin "8") (pinfunction "8_8") (pintype "passive"))
    )
    (net (code "49") (name "unconnected-(X9-Pad10)") (class "Default")
      (node (ref "X9") (pin "10") (pinfunction "10_10") (pintype "passive"))
    )
    (net (code "50") (name "unconnected-(X9-Pad11)") (class "Default")
      (node (ref "X9") (pin "11") (pinfunction "11_11") (pintype "passive"))
    )
    (net (code "51") (name "unconnected-(X9-Pad12)") (class "Default")
      (node (ref "X9") (pin "12") (pinfunction "12_12") (pintype "passive"))
    )
    (net (code "52") (name "unconnected-(X9-Pad13)") (class "Default")
      (node (ref "X9") (pin "13") (pinfunction "13_13") (pintype "passive"))
    )
    (net (code "53") (name "unconnected-(X9-Pad15)") (class "Default")
      (node (ref "X9") (pin "15") (pinfunction "15_15") (pintype "passive"))
    )
    (net (code "54") (name "unconnected-(X9-Pad16)") (class "Default")
      (node (ref "X9") (pin "16") (pinfunction "16_16") (pintype "passive"))
    )
    (net (code "55") (name "unconnected-(X9-Pad18)") (class "Default")
      (node (ref "X9") (pin "18") (pinfunction "18_18") (pintype "passive"))
    )
    (net (code "56") (name "unconnected-(X9-Pad19)") (class "Default")
      (node (ref "X9") (pin "19") (pinfunction "19_19") (pintype "passive"))
    )
    (net (code "57") (name "unconnected-(X9-Pad21)") (class "Default")
      (node (ref "X9") (pin "21") (pinfunction "21_21") (pintype "passive"))
    )
    (net (code "58") (name "unconnected-(X9-Pad22)") (class "Default")
      (node (ref "X9") (pin "22") (pinfunction "22_22") (pintype "passive"))
    )
    (net (code "59") (name "unconnected-(X9-Pad23)") (class "Default")
      (node (ref "X9") (pin "23") (pinfunction "23_23") (pintype "passive"))
    )
    (net (code "60") (name "unconnected-(X9-Pad24)") (class "Default")
      (node (ref "X9") (pin "24") (pinfunction "24_24") (pintype "passive"))
    )
    (net (code "61") (name "unconnected-(X9-Pad26)") (class "Default")
      (node (ref "X9") (pin "26") (pinfunction "26_26") (pintype "passive"))
    )
    (net (code "62") (name "unconnected-(X9-Pad27)") (class "Default")
      (node (ref "X9") (pin "27") (pinfunction "27_27") (pintype "passive"))
    )
    (net (code "63") (name "unconnected-(X9-Pad28)") (class "Default")
      (node (ref "X9") (pin "28") (pinfunction "28_28") (pintype "passive"))
    )
    (net (code "64") (name "unconnected-(X9-Pad29)") (class "Default")
      (node (ref "X9") (pin "29") (pinfunction "29_29") (pintype "passive"))
    )
    (net (code "65") (name "unconnected-(X9-Pad31)") (class "Default")
      (node (ref "X9") (pin "31") (pinfunction "31_31") (pintype "passive"))
    )
    (net (code "66") (name "unconnected-(X9-Pad32)") (class "Default")
      (node (ref "X9") (pin "32") (pinfunction "32_32") (pintype "passive"))
    )
    (net (code "67") (name "unconnected-(X9-Pad33)") (class "Default")
      (node (ref "X9") (pin "33") (pinfunction "33_33") (pintype "passive"))
    )
    (net (code "68") (name "unconnected-(X9-Pad35)") (class "Default")
      (node (ref "X9") (pin "35") (pinfunction "35_35") (pintype "passive"))
    )
    (net (code "69") (name "unconnected-(X9-Pad36)") (class "Default")
      (node (ref "X9") (pin "36") (pinfunction "36_36") (pintype "passive"))
    )
    (net (code "70") (name "unconnected-(X9-Pad37)") (class "Default")
      (node (ref "X9") (pin "37") (pinfunction "37_37") (pintype "passive"))
    )
    (net (code "71") (name "unconnected-(X9-Pad38)") (class "Default")
      (node (ref "X9") (pin "38") (pinfunction "38_38") (pintype "passive"))
    )
    (net (code "72") (name "unconnected-(X9-Pad40)") (class "Default")
      (node (ref "X9") (pin "40") (pinfunction "40_40") (pintype "passive"))
    )
  )
)
